# blink1mk3_002_3535.net
KiCad netlist of a schematic drawn in EAGLE
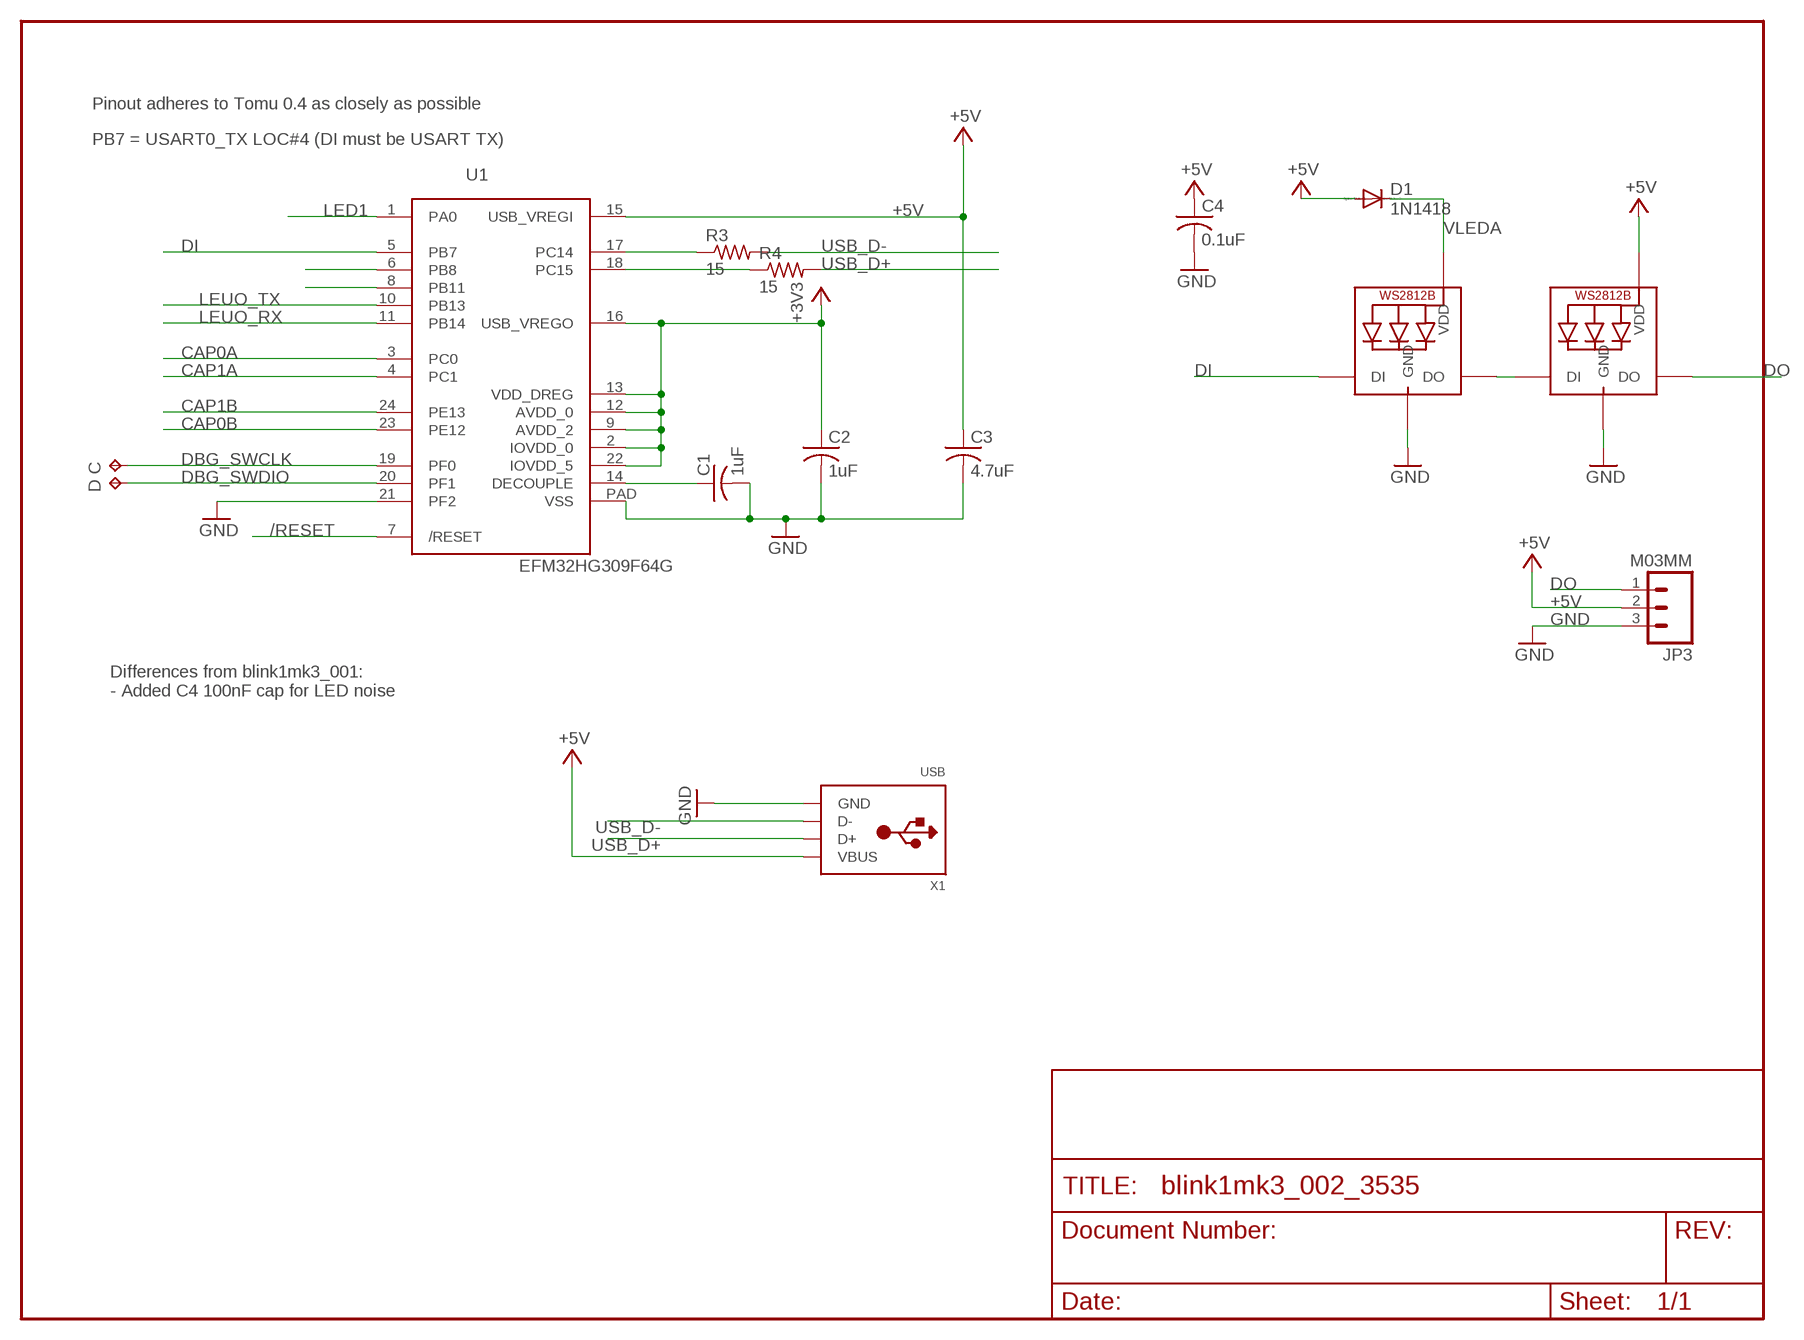
[diagram p0: schematic, sheet 1]

(export (version "E")
  (design (tool "Eeschema 10.0.6"))
  (components
    (comp (ref "C")
      (value "TPTP10R")
      (footprint "eagle-import:TP10R")
      (libsource (lib "eagle-import") (part "TPTP10R"))
    )
    (comp (ref "C1")
      (value "1uF")
      (footprint "eagle-import:C0402")
      (libsource (lib "eagle-import") (part "C-USC0402"))
    )
    (comp (ref "C2")
      (value "1uF")
      (footprint "eagle-import:C0402")
      (libsource (lib "eagle-import") (part "C-USC0402"))
    )
    (comp (ref "C3")
      (value "4.7uF")
      (footprint "eagle-import:C0402")
      (libsource (lib "eagle-import") (part "C-USC0402"))
    )
    (comp (ref "C4")
      (value "0.1uF")
      (footprint "eagle-import:C0402")
      (libsource (lib "eagle-import") (part "C-USC0402"))
    )
    (comp (ref "D")
      (value "TPTP10R")
      (footprint "eagle-import:TP10R")
      (libsource (lib "eagle-import") (part "TPTP10R"))
    )
    (comp (ref "D1")
      (value "1N1418")
      (footprint "eagle-import:SOD523")
      (libsource (lib "eagle-import") (part "DIODE-SOD523"))
    )
    (comp (ref "JP3")
      (value "M03MM")
      (footprint "eagle-import:1X03-1.5MM")
      (libsource (lib "eagle-import") (part "M03MM"))
    )
    (comp (ref "LED1")
      (value "WS2812B3535")
      (footprint "eagle-import:LED3535")
      (libsource (lib "eagle-import") (part "WS2812B3535"))
    )
    (comp (ref "LED2")
      (value "WS2812B3535")
      (footprint "eagle-import:LED3535")
      (libsource (lib "eagle-import") (part "WS2812B3535"))
    )
    (comp (ref "R3")
      (value "15")
      (footprint "eagle-import:R0402")
      (libsource (lib "eagle-import") (part "R-US_R0402"))
    )
    (comp (ref "R4")
      (value "15")
      (footprint "eagle-import:R0402")
      (libsource (lib "eagle-import") (part "R-US_R0402"))
    )
    (comp (ref "U1")
      (value "EFM32HG309F64G")
      (footprint "eagle-import:QFN24PAD")
      (libsource (lib "eagle-import") (part "EFM32HG309F64G"))
    )
    (comp (ref "X1")
      (value "USB")
      (footprint "eagle-import:MOLEX-48037-1000")
      (libsource (lib "eagle-import") (part "USB"))
    )
  )
  (nets
    (net (code "1") (name "+3V3") (class "Default")
      (node (ref "C2") (pin "1") (pinfunction "1_1") (pintype "passive"))
      (node (ref "U1") (pin "12") (pinfunction "AVDD_0_12") (pintype "bidirectional"))
      (node (ref "U1") (pin "13") (pinfunction "VDD_DREG_13") (pintype "bidirectional"))
      (node (ref "U1") (pin "16") (pinfunction "USB_VREGO_16") (pintype "bidirectional"))
      (node (ref "U1") (pin "2") (pinfunction "IOVDD_0_2") (pintype "bidirectional"))
      (node (ref "U1") (pin "22") (pinfunction "IOVDD_5_22") (pintype "bidirectional"))
      (node (ref "U1") (pin "9") (pinfunction "AVDD_2_9") (pintype "bidirectional"))
    )
    (net (code "2") (name "+5V") (class "Default")
      (node (ref "C3") (pin "1") (pinfunction "1_1") (pintype "passive"))
      (node (ref "C4") (pin "1") (pinfunction "1_1") (pintype "passive"))
      (node (ref "D1") (pin "A") (pinfunction "A_A") (pintype "passive"))
      (node (ref "JP3") (pin "2") (pinfunction "2_2") (pintype "passive"))
      (node (ref "LED2") (pin "2") (pinfunction "VDD_2") (pintype "power_in"))
      (node (ref "U1") (pin "15") (pinfunction "USB_VREGI_15") (pintype "bidirectional"))
      (node (ref "X1") (pin "1") (pinfunction "VBUS_1") (pintype "power_in"))
    )
    (net (code "3") (name "/CAP0A") (class "Default")
      (node (ref "U1") (pin "3") (pinfunction "PC0_3") (pintype "bidirectional"))
    )
    (net (code "4") (name "/CAP0B") (class "Default")
      (node (ref "U1") (pin "23") (pinfunction "PE12_23") (pintype "bidirectional"))
    )
    (net (code "5") (name "/CAP1A") (class "Default")
      (node (ref "U1") (pin "4") (pinfunction "PC1_4") (pintype "bidirectional"))
    )
    (net (code "6") (name "/CAP1B") (class "Default")
      (node (ref "U1") (pin "24") (pinfunction "PE13_24") (pintype "bidirectional"))
    )
    (net (code "7") (name "/DBG_SWCLK") (class "Default")
      (node (ref "C") (pin "TP") (pinfunction "TP_TP") (pintype "input"))
      (node (ref "U1") (pin "19") (pinfunction "PF0_19") (pintype "bidirectional"))
    )
    (net (code "8") (name "/DBG_SWDIO") (class "Default")
      (node (ref "D") (pin "TP") (pinfunction "TP_TP") (pintype "input"))
      (node (ref "U1") (pin "20") (pinfunction "PF1_20") (pintype "bidirectional"))
    )
    (net (code "9") (name "/DI") (class "Default")
      (node (ref "LED1") (pin "1") (pinfunction "DI_1") (pintype "input"))
      (node (ref "U1") (pin "5") (pinfunction "PB7_5") (pintype "bidirectional"))
    )
    (net (code "10") (name "/DO") (class "Default")
      (node (ref "JP3") (pin "1") (pinfunction "1_1") (pintype "passive"))
      (node (ref "LED2") (pin "3") (pinfunction "DO_3") (pintype "output"))
    )
    (net (code "11") (name "/LED1") (class "Default")
      (node (ref "U1") (pin "1") (pinfunction "PA0_1") (pintype "bidirectional"))
    )
    (net (code "12") (name "/LEUO_RX") (class "Default")
      (node (ref "U1") (pin "11") (pinfunction "PB14_11") (pintype "bidirectional"))
    )
    (net (code "13") (name "/LEUO_TX") (class "Default")
      (node (ref "U1") (pin "10") (pinfunction "PB13_10") (pintype "bidirectional"))
    )
    (net (code "14") (name "/USB_D+") (class "Default")
      (node (ref "R4") (pin "2") (pinfunction "2_2") (pintype "passive"))
      (node (ref "X1") (pin "3") (pinfunction "D+_3") (pintype "bidirectional"))
    )
    (net (code "15") (name "/USB_D-") (class "Default")
      (node (ref "R3") (pin "2") (pinfunction "2_2") (pintype "passive"))
      (node (ref "X1") (pin "2") (pinfunction "D-_2") (pintype "bidirectional"))
    )
    (net (code "16") (name "/VLEDA") (class "Default")
      (node (ref "D1") (pin "C") (pinfunction "C_C") (pintype "passive"))
      (node (ref "LED1") (pin "2") (pinfunction "VDD_2") (pintype "power_in"))
    )
    (net (code "17") (name "/{slash}RESET") (class "Default")
      (node (ref "U1") (pin "7") (pinfunction "/RESET_7") (pintype "bidirectional"))
    )
    (net (code "18") (name "GND") (class "Default")
      (node (ref "C1") (pin "2") (pinfunction "2_2") (pintype "passive"))
      (node (ref "C2") (pin "2") (pinfunction "2_2") (pintype "passive"))
      (node (ref "C3") (pin "2") (pinfunction "2_2") (pintype "passive"))
      (node (ref "C4") (pin "2") (pinfunction "2_2") (pintype "passive"))
      (node (ref "JP3") (pin "3") (pinfunction "3_3") (pintype "passive"))
      (node (ref "LED1") (pin "4") (pinfunction "GND_4") (pintype "power_in"))
      (node (ref "LED2") (pin "4") (pinfunction "GND_4") (pintype "power_in"))
      (node (ref "U1") (pin "21") (pinfunction "PF2_21") (pintype "bidirectional"))
      (node (ref "U1") (pin "PAD") (pinfunction "VSS_PAD") (pintype "bidirectional"))
      (node (ref "X1") (pin "4") (pinfunction "GND_4") (pintype "power_in"))
    )
    (net (code "19") (name "Net-(LED1-DO)") (class "Default")
      (node (ref "LED1") (pin "3") (pinfunction "DO_3") (pintype "output"))
      (node (ref "LED2") (pin "1") (pinfunction "DI_1") (pintype "input"))
    )
    (net (code "20") (name "Net-(U1-DECOUPLE)") (class "Default")
      (node (ref "C1") (pin "1") (pinfunction "1_1") (pintype "passive"))
      (node (ref "U1") (pin "14") (pinfunction "DECOUPLE_14") (pintype "bidirectional"))
    )
    (net (code "21") (name "Net-(U1-PC14)") (class "Default")
      (node (ref "R3") (pin "1") (pinfunction "1_1") (pintype "passive"))
      (node (ref "U1") (pin "17") (pinfunction "PC14_17") (pintype "bidirectional"))
    )
    (net (code "22") (name "Net-(U1-PC15)") (class "Default")
      (node (ref "R4") (pin "1") (pinfunction "1_1") (pintype "passive"))
      (node (ref "U1") (pin "18") (pinfunction "PC15_18") (pintype "bidirectional"))
    )
    (net (code "23") (name "unconnected-(U1-PB8-Pad6)") (class "Default")
      (node (ref "U1") (pin "6") (pinfunction "PB8_6") (pintype "bidirectional"))
    )
    (net (code "24") (name "unconnected-(U1-PB11-Pad8)") (class "Default")
      (node (ref "U1") (pin "8") (pinfunction "PB11_8") (pintype "bidirectional"))
    )
  )
)
